# PCB-DISP64x32.net
KiCad netlist of a schematic drawn in EAGLE
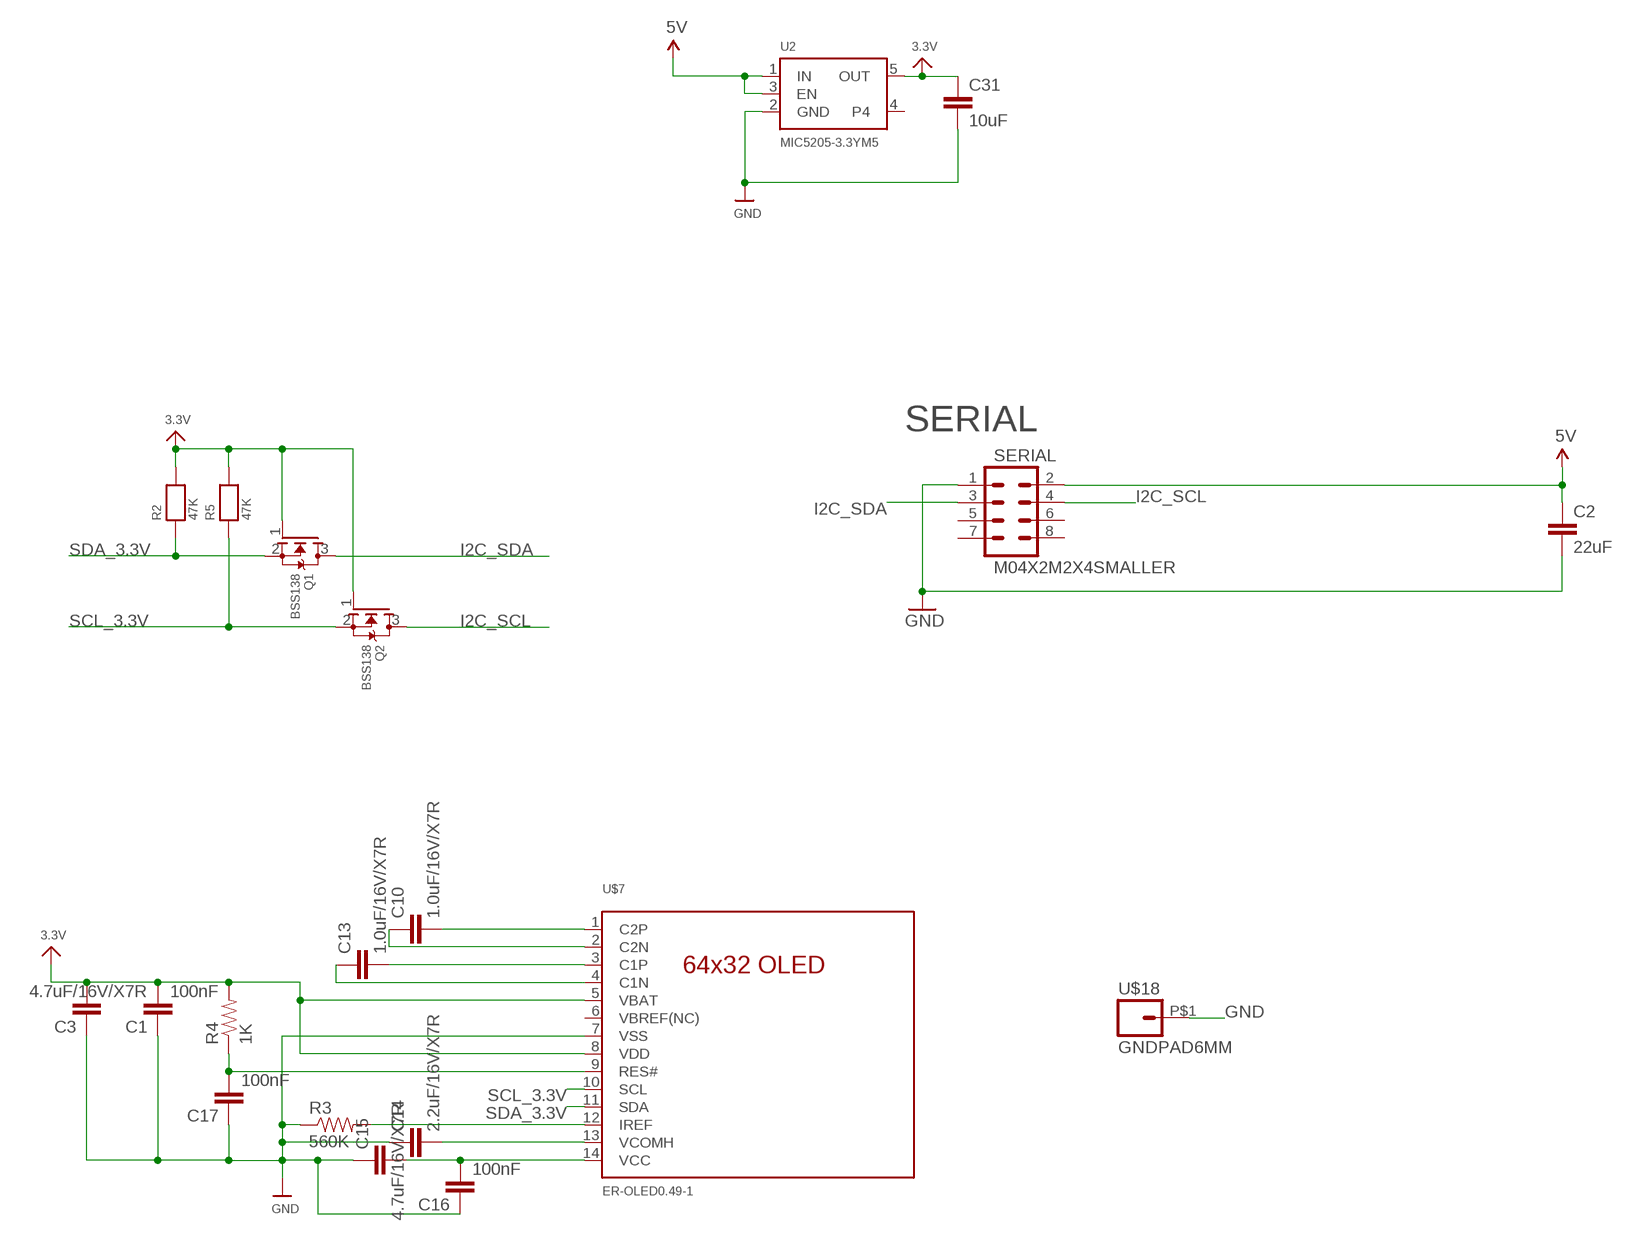
[diagram p0: schematic, sheet 1]

(export (version "E")
  (design (tool "Eeschema 10.0.6"))
  (components
    (comp (ref "C1")
      (value "100nF")
      (footprint "eagle-import:0603-CAP")
      (libsource (lib "eagle-import") (part "CAP0603-CAP"))
    )
    (comp (ref "C2")
      (value "22uF")
      (footprint "eagle-import:0805")
      (libsource (lib "eagle-import") (part "CAP0805"))
    )
    (comp (ref "C3")
      (value "4.7uF/16V/X7R")
      (footprint "eagle-import:0603-CAP")
      (libsource (lib "eagle-import") (part "CAP0603-CAP"))
    )
    (comp (ref "C10")
      (value "1.0uF/16V/X7R")
      (footprint "eagle-import:0603-CAP")
      (libsource (lib "eagle-import") (part "CAP0603-CAP"))
    )
    (comp (ref "C13")
      (value "1.0uF/16V/X7R")
      (footprint "eagle-import:0603-CAP")
      (libsource (lib "eagle-import") (part "CAP0603-CAP"))
    )
    (comp (ref "C14")
      (value "2.2uF/16V/X7R")
      (footprint "eagle-import:0603-CAP")
      (libsource (lib "eagle-import") (part "CAP0603-CAP"))
    )
    (comp (ref "C15")
      (value "4.7uF/16V/X7R")
      (footprint "eagle-import:0603-CAP")
      (libsource (lib "eagle-import") (part "CAP0603-CAP"))
    )
    (comp (ref "C16")
      (value "100nF")
      (footprint "eagle-import:0603-CAP")
      (libsource (lib "eagle-import") (part "CAP0603-CAP"))
    )
    (comp (ref "C17")
      (value "100nF")
      (footprint "eagle-import:0603-CAP")
      (libsource (lib "eagle-import") (part "CAP0603-CAP"))
    )
    (comp (ref "C31")
      (value "10uF")
      (footprint "eagle-import:0805")
      (libsource (lib "eagle-import") (part "CAP0805"))
    )
    (comp (ref "Q1")
      (value "BSS138")
      (footprint "eagle-import:SOT23-R")
      (libsource (lib "eagle-import") (part "MOSFET-NREFLOW"))
    )
    (comp (ref "Q2")
      (value "BSS138")
      (footprint "eagle-import:SOT23-R")
      (libsource (lib "eagle-import") (part "MOSFET-NREFLOW"))
    )
    (comp (ref "R2")
      (value "47K")
      (footprint "eagle-import:0603")
      (libsource (lib "eagle-import") (part "RESISTOR0603"))
    )
    (comp (ref "R3")
      (value "560K")
      (footprint "eagle-import:0603-RES")
      (libsource (lib "eagle-import") (part "RESISTOR0603-RES"))
    )
    (comp (ref "R4")
      (value "1K")
      (footprint "eagle-import:0603-RES")
      (libsource (lib "eagle-import") (part "RESISTOR0603-RES"))
    )
    (comp (ref "R5")
      (value "47K")
      (footprint "eagle-import:0603")
      (libsource (lib "eagle-import") (part "RESISTOR0603"))
    )
    (comp (ref "SERIAL")
      (value "M04X2M2X4SMALLER")
      (footprint "eagle-import:M2X4SMALLER")
      (libsource (lib "eagle-import") (part "M04X2M2X4SMALLER"))
    )
    (comp (ref "U$7")
      (value "ER-OLED0.49-1")
      (footprint "eagle-import:ER-OLED0.49-1_WRAPAROUND")
      (libsource (lib "eagle-import") (part "ER-OLED0.49-1"))
    )
    (comp (ref "U$18")
      (value "GNDPAD6MM")
      (footprint "eagle-import:3.2MMPAD6MM")
      (libsource (lib "eagle-import") (part "GNDPAD6MM"))
    )
    (comp (ref "U2")
      (value "MIC5205-3.3YM5")
      (footprint "eagle-import:SOT23-5")
      (libsource (lib "eagle-import") (part "VREG_SOT23-5"))
    )
  )
  (nets
    (net (code "1") (name "3.3V") (class "Default")
      (node (ref "C1") (pin "2") (pinfunction "2_2") (pintype "passive"))
      (node (ref "C3") (pin "2") (pinfunction "2_2") (pintype "passive"))
      (node (ref "C31") (pin "1") (pinfunction "1_1") (pintype "passive"))
      (node (ref "Q1") (pin "1") (pinfunction "G_1") (pintype "bidirectional"))
      (node (ref "Q2") (pin "1") (pinfunction "G_1") (pintype "bidirectional"))
      (node (ref "R2") (pin "2") (pinfunction "2_2") (pintype "passive"))
      (node (ref "R4") (pin "2") (pinfunction "2_2") (pintype "passive"))
      (node (ref "R5") (pin "2") (pinfunction "2_2") (pintype "passive"))
      (node (ref "U$7") (pin "5") (pinfunction "VBAT_5") (pintype "power_in"))
      (node (ref "U$7") (pin "8") (pinfunction "VDD_8") (pintype "power_in"))
      (node (ref "U2") (pin "5") (pinfunction "OUT_5") (pintype "bidirectional"))
    )
    (net (code "2") (name "5V") (class "Default")
      (node (ref "C2") (pin "1") (pinfunction "1_1") (pintype "passive"))
      (node (ref "SERIAL") (pin "2") (pinfunction "2_2") (pintype "passive"))
      (node (ref "U2") (pin "1") (pinfunction "IN_1") (pintype "bidirectional"))
      (node (ref "U2") (pin "3") (pinfunction "EN_3") (pintype "bidirectional"))
    )
    (net (code "3") (name "GND") (class "Default")
      (node (ref "C1") (pin "1") (pinfunction "1_1") (pintype "passive"))
      (node (ref "C14") (pin "1") (pinfunction "1_1") (pintype "passive"))
      (node (ref "C15") (pin "1") (pinfunction "1_1") (pintype "passive"))
      (node (ref "C16") (pin "1") (pinfunction "1_1") (pintype "passive"))
      (node (ref "C17") (pin "1") (pinfunction "1_1") (pintype "passive"))
      (node (ref "C2") (pin "2") (pinfunction "2_2") (pintype "passive"))
      (node (ref "C3") (pin "1") (pinfunction "1_1") (pintype "passive"))
      (node (ref "C31") (pin "2") (pinfunction "2_2") (pintype "passive"))
      (node (ref "R3") (pin "1") (pinfunction "1_1") (pintype "passive"))
      (node (ref "SERIAL") (pin "1") (pinfunction "1_1") (pintype "passive"))
      (node (ref "U$18") (pin "P$1") (pinfunction "1_P$1") (pintype "passive"))
      (node (ref "U$7") (pin "7") (pinfunction "VSS_7") (pintype "power_in"))
      (node (ref "U2") (pin "2") (pinfunction "GND_2") (pintype "bidirectional"))
    )
    (net (code "4") (name "I2C_SCL") (class "Default")
      (node (ref "Q2") (pin "3") (pinfunction "D_3") (pintype "bidirectional"))
      (node (ref "SERIAL") (pin "4") (pinfunction "4_4") (pintype "passive"))
    )
    (net (code "5") (name "I2C_SDA") (class "Default")
      (node (ref "Q1") (pin "3") (pinfunction "D_3") (pintype "bidirectional"))
      (node (ref "SERIAL") (pin "3") (pinfunction "3_3") (pintype "passive"))
    )
    (net (code "6") (name "Net-(U$7-C1N)") (class "Default")
      (node (ref "C13") (pin "1") (pinfunction "1_1") (pintype "passive"))
      (node (ref "U$7") (pin "4") (pinfunction "C1N_4") (pintype "bidirectional"))
    )
    (net (code "7") (name "Net-(U$7-C1P)") (class "Default")
      (node (ref "C13") (pin "2") (pinfunction "2_2") (pintype "passive"))
      (node (ref "U$7") (pin "3") (pinfunction "C1P_3") (pintype "bidirectional"))
    )
    (net (code "8") (name "Net-(U$7-C2N)") (class "Default")
      (node (ref "C10") (pin "1") (pinfunction "1_1") (pintype "passive"))
      (node (ref "U$7") (pin "2") (pinfunction "C2N_2") (pintype "bidirectional"))
    )
    (net (code "9") (name "Net-(U$7-C2P)") (class "Default")
      (node (ref "C10") (pin "2") (pinfunction "2_2") (pintype "passive"))
      (node (ref "U$7") (pin "1") (pinfunction "C2P_1") (pintype "bidirectional"))
    )
    (net (code "10") (name "Net-(U$7-IREF)") (class "Default")
      (node (ref "R3") (pin "2") (pinfunction "2_2") (pintype "passive"))
      (node (ref "U$7") (pin "12") (pinfunction "IREF_12") (pintype "input"))
    )
    (net (code "11") (name "Net-(U$7-RES#)") (class "Default")
      (node (ref "C17") (pin "2") (pinfunction "2_2") (pintype "passive"))
      (node (ref "R4") (pin "1") (pinfunction "1_1") (pintype "passive"))
      (node (ref "U$7") (pin "9") (pinfunction "RES#_9") (pintype "input"))
    )
    (net (code "12") (name "Net-(U$7-VCC)") (class "Default")
      (node (ref "C15") (pin "2") (pinfunction "2_2") (pintype "passive"))
      (node (ref "C16") (pin "2") (pinfunction "2_2") (pintype "passive"))
      (node (ref "U$7") (pin "14") (pinfunction "VCC_14") (pintype "power_in"))
    )
    (net (code "13") (name "Net-(U$7-VCOMH)") (class "Default")
      (node (ref "C14") (pin "2") (pinfunction "2_2") (pintype "passive"))
      (node (ref "U$7") (pin "13") (pinfunction "VCOMH_13") (pintype "output"))
    )
    (net (code "14") (name "SCL_3.3V") (class "Default")
      (node (ref "Q2") (pin "2") (pinfunction "S_2") (pintype "bidirectional"))
      (node (ref "R5") (pin "1") (pinfunction "1_1") (pintype "passive"))
      (node (ref "U$7") (pin "10") (pinfunction "SCL_10") (pintype "input"))
    )
    (net (code "15") (name "SDA_3.3V") (class "Default")
      (node (ref "Q1") (pin "2") (pinfunction "S_2") (pintype "bidirectional"))
      (node (ref "R2") (pin "1") (pinfunction "1_1") (pintype "passive"))
      (node (ref "U$7") (pin "11") (pinfunction "SDA_11") (pintype "input"))
    )
    (net (code "16") (name "unconnected-(SERIAL-Pad5)") (class "Default")
      (node (ref "SERIAL") (pin "5") (pinfunction "5_5") (pintype "passive"))
    )
    (net (code "17") (name "unconnected-(SERIAL-Pad6)") (class "Default")
      (node (ref "SERIAL") (pin "6") (pinfunction "6_6") (pintype "passive"))
    )
    (net (code "18") (name "unconnected-(SERIAL-Pad7)") (class "Default")
      (node (ref "SERIAL") (pin "7") (pinfunction "7_7") (pintype "passive"))
    )
    (net (code "19") (name "unconnected-(SERIAL-Pad8)") (class "Default")
      (node (ref "SERIAL") (pin "8") (pinfunction "8_8") (pintype "passive"))
    )
    (net (code "20") (name "unconnected-(U$7-VBREF(NC)-Pad6)") (class "Default")
      (node (ref "U$7") (pin "6") (pinfunction "VBREF(NC)_6") (pintype "no_connect"))
    )
    (net (code "21") (name "unconnected-(U2-P4-Pad4)") (class "Default")
      (node (ref "U2") (pin "4") (pinfunction "P4_4") (pintype "bidirectional"))
    )
  )
)
